# Sheet_1_2021-08-17.net
KiCad netlist of a schematic drawn in Altium Designer
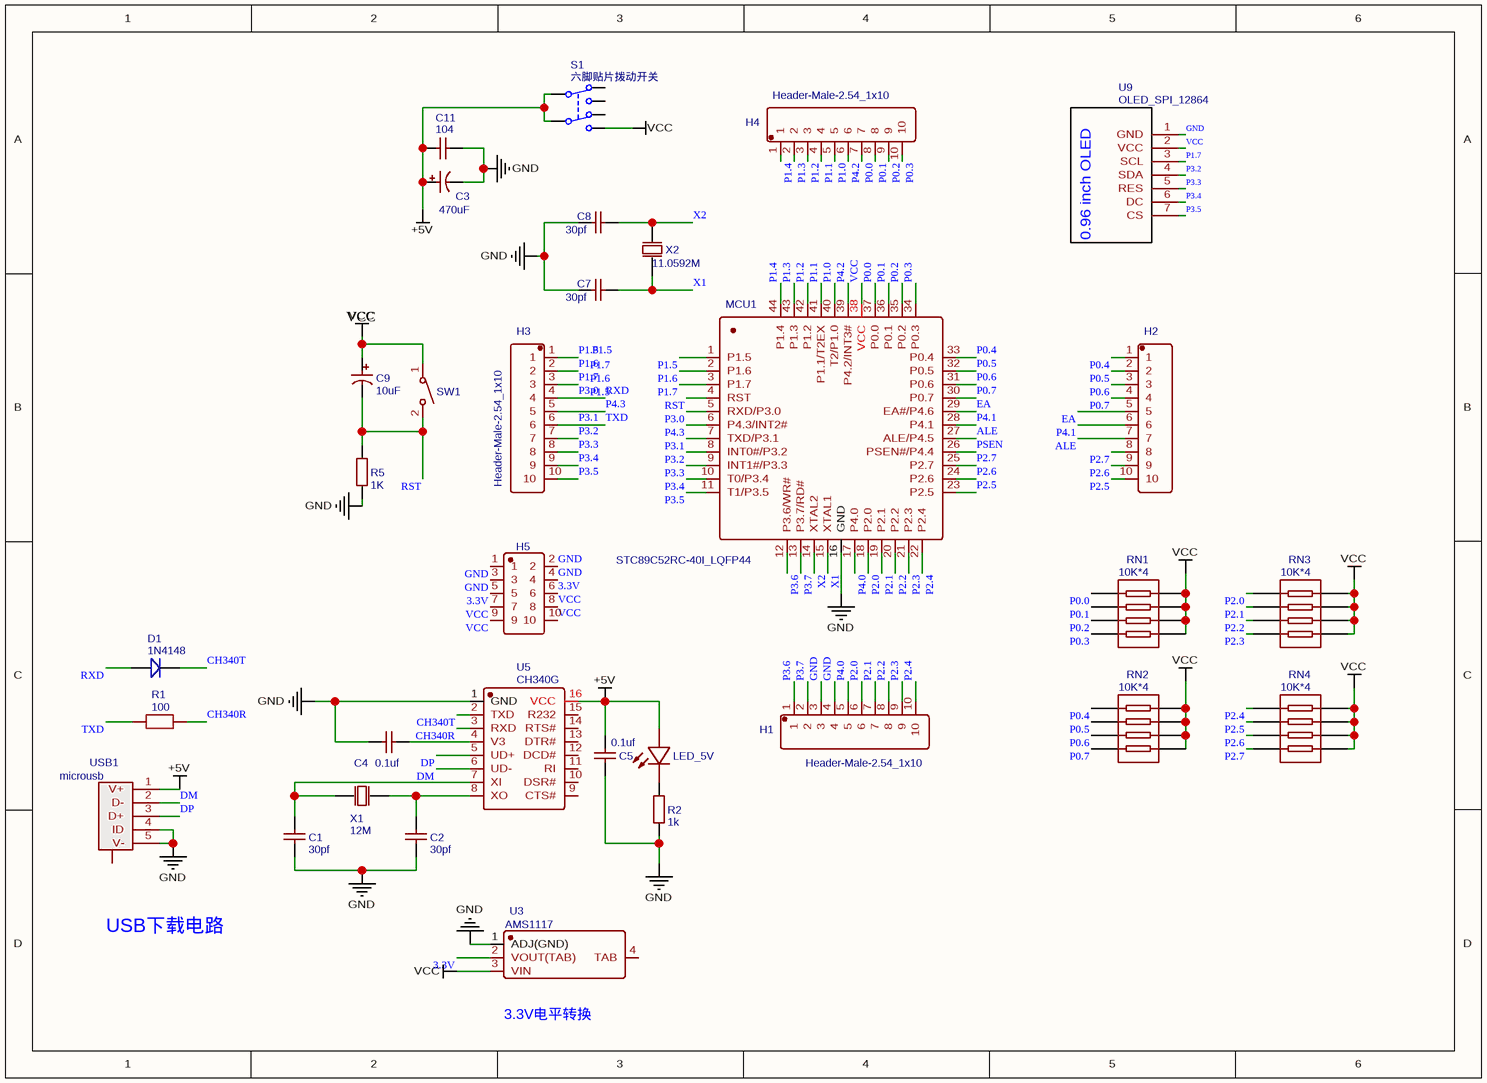
[diagram p0: Sheet_1_2021-08-17.schdoc]

(export (version "E")
  (design (tool "Eeschema 10.0.6"))
  (components
    (comp (ref "C1")
      (value "30pf")
      (fields
        (field (name "BOM_SUPPLIER PART") "C305730")
        (field (name "BOM_MANUFACTURER PART") "CC81-M6S2L1B101KSE")
        (field (name "CONTRIBUTOR") "LCSC")
      )
      (libsource (lib "altium-import") (part "root_1_30pf_"))
    )
    (comp (ref "C2")
      (value "30pf")
      (fields
        (field (name "BOM_SUPPLIER PART") "C305730")
        (field (name "BOM_MANUFACTURER PART") "CC81-M6S2L1B101KSE")
        (field (name "CONTRIBUTOR") "LCSC")
      )
      (libsource (lib "altium-import") (part "root_3_30pf_"))
    )
    (comp (ref "C3")
      (value "470uF")
      (fields
        (field (name "BOM_MANUFACTURER PART") "VEJ471M1CTR-0810")
        (field (name "BOM_SUPPLIER PART") "C176671")
        (field (name "CONTRIBUTOR") "LCSC")
      )
      (libsource (lib "altium-import") (part "root_1_470uF_"))
    )
    (comp (ref "C4")
      (value "0.1uf")
      (fields
        (field (name "BOM_SUPPLIER PART") "C305730")
        (field (name "BOM_MANUFACTURER PART") "CC81-M6S2L1B101KSE")
        (field (name "CONTRIBUTOR") "LCSC")
      )
      (libsource (lib "altium-import") (part "root_2_0.1uf_"))
    )
    (comp (ref "C5")
      (value "0.1uf")
      (fields
        (field (name "BOM_SUPPLIER PART") "C305730")
        (field (name "BOM_MANUFACTURER PART") "CC81-M6S2L1B101KSE")
        (field (name "CONTRIBUTOR") "LCSC")
      )
      (libsource (lib "altium-import") (part "root_1_0.1uf_"))
    )
    (comp (ref "C7")
      (value "30pf")
      (fields
        (field (name "BOM_SUPPLIER PART") "C305730")
        (field (name "BOM_MANUFACTURER PART") "CC81-M6S2L1B101KSE")
        (field (name "CONTRIBUTOR") "LCSC")
      )
      (libsource (lib "altium-import") (part "root_0_30pf_"))
    )
    (comp (ref "C8")
      (value "30pf")
      (fields
        (field (name "BOM_SUPPLIER PART") "C305730")
        (field (name "BOM_MANUFACTURER PART") "CC81-M6S2L1B101KSE")
        (field (name "CONTRIBUTOR") "LCSC")
      )
      (libsource (lib "altium-import") (part "root_0_30pf_"))
    )
    (comp (ref "C9")
      (value "10uF")
      (fields
        (field (name "BOM_MANUFACTURER PART") "VE-100M1ETR-0405")
        (field (name "BOM_SUPPLIER PART") "C134721")
        (field (name "CONTRIBUTOR") "LCSC")
      )
      (libsource (lib "altium-import") (part "root_0_10uF_"))
    )
    (comp (ref "C11")
      (value "104")
      (fields
        (field (name "BOM_SUPPLIER PART") "C305730")
        (field (name "BOM_MANUFACTURER PART") "CC81-M6S2L1B101KSE")
        (field (name "CONTRIBUTOR") "LCSC")
      )
      (libsource (lib "altium-import") (part "root_2_104_"))
    )
    (comp (ref "D1")
      (value "1N4148")
      (fields (field (name "CONTRIBUTOR") "NJDZ"))
      (libsource (lib "altium-import") (part "root_0_1N4148_"))
    )
    (comp (ref "H1")
      (value "Header-Male-2.54_1x10")
      (fields
        (field (name "BOM_MANUFACTURER PART") "Headers  Pins2.54mm1*10P")
        (field (name "BOM_SUPPLIER PART") "C57369")
      )
      (libsource (lib "altium-import") (part "root_3_Header-Male-2.54_1x10_"))
    )
    (comp (ref "H2")
      (value "Header-Male-2.54_1x10")
      (fields
        (field (name "BOM_MANUFACTURER PART") "Headers  Pins2.54mm1*10P")
        (field (name "BOM_SUPPLIER PART") "C57369")
      )
      (libsource (lib "altium-import") (part "root_0_Header-Male-2.54_1x10_"))
    )
    (comp (ref "H3")
      (value "Header-Male-2.54_1x10")
      (fields
        (field (name "BOM_MANUFACTURER PART") "Headers  Pins2.54mm1*10P")
        (field (name "BOM_SUPPLIER PART") "C57369")
      )
      (libsource (lib "") (part "root_0_Header-Male-2.54_1x10__1"))
    )
    (comp (ref "H4")
      (value "Header-Male-2.54_1x10")
      (fields
        (field (name "BOM_MANUFACTURER PART") "Headers  Pins2.54mm1*10P")
        (field (name "BOM_SUPPLIER PART") "C57369")
      )
      (libsource (lib "altium-import") (part "root_1_Header-Male-2.54_1x10_"))
    )
    (comp (ref "H5")
      (value "X6521FV-2×05-C85D32")
      (fields (field (name "BOM_SUPPLIER PART") "C718231") (field (name "CONTRIBUTOR") "LCSC"))
      (libsource (lib "altium-import") (part "root_0_X6521FV-2×05-C85D32_"))
    )
    (comp (ref "LED_5V")
      (value "led Green")
      (fields (field (name "BOM_SUPPLIER PART") "C14641"))
      (libsource (lib "altium-import") (part "root_1_led Green_"))
    )
    (comp (ref "MCU1")
      (value "STC89C52RC-40I_LQFP44")
      (fields
        (field (name "BOM_MANUFACTURER PART") "STC89C52RC-40I")
        (field (name "BOM_SUPPLIER PART") "C8707")
      )
      (libsource (lib "altium-import") (part "root_0_STC89C52RC-40I_LQFP44_"))
    )
    (comp (ref "R1")
      (value "100")
      (fields (field (name "CONTRIBUTOR") "LCEDA_Lib"))
      (libsource (lib "altium-import") (part "root_0_100_"))
    )
    (comp (ref "R2")
      (value "1k")
      (fields
        (field (name "BOM_MANUFACTURER PART") "0603WAF1000T5E")
        (field (name "BOM_SUPPLIER PART") "C22775")
      )
      (libsource (lib "altium-import") (part "root_1_1k_"))
    )
    (comp (ref "R5")
      (value "1K")
      (fields
        (field (name "BOM_MANUFACTURER PART") "0603WAF1000T5E")
        (field (name "BOM_SUPPLIER PART") "C22775")
      )
      (libsource (lib "altium-import") (part "root_1_1K_"))
    )
    (comp (ref "RN1")
      (value "10K*4")
      (fields
        (field (name "BOM_MANUFACTURER PART") "RC-ML08W103JT")
        (field (name "BOM_SUPPLIER PART") "C69593")
        (field (name "CONTRIBUTOR") "amwhibo")
      )
      (libsource (lib "altium-import") (part "root_1_10K*4_"))
    )
    (comp (ref "RN2")
      (value "10K*4")
      (fields
        (field (name "BOM_MANUFACTURER PART") "RC-ML08W103JT")
        (field (name "BOM_SUPPLIER PART") "C69593")
        (field (name "CONTRIBUTOR") "amwhibo")
      )
      (libsource (lib "altium-import") (part "root_1_10K*4_"))
    )
    (comp (ref "RN3")
      (value "10K*4")
      (fields
        (field (name "BOM_MANUFACTURER PART") "RC-ML08W103JT")
        (field (name "BOM_SUPPLIER PART") "C69593")
        (field (name "CONTRIBUTOR") "amwhibo")
      )
      (libsource (lib "altium-import") (part "root_1_10K*4_"))
    )
    (comp (ref "RN4")
      (value "10K*4")
      (fields
        (field (name "BOM_MANUFACTURER PART") "RC-ML08W103JT")
        (field (name "BOM_SUPPLIER PART") "C69593")
        (field (name "CONTRIBUTOR") "amwhibo")
      )
      (libsource (lib "altium-import") (part "root_1_10K*4_"))
    )
    (comp (ref "S1")
      (value "六脚贴片拨动开关")
      (fields (field (name "CONTRIBUTOR") "yds432427"))
      (libsource (lib "altium-import") (part "root_0_六脚贴片拨动开关_"))
    )
    (comp (ref "SW1")
      (value "UK-B0240-W-250-JZ")
      (fields (field (name "BOM_SUPPLIER PART") "C780530") (field (name "CONTRIBUTOR") "LCSC"))
      (libsource (lib "altium-import") (part "root_3_UK-B0240-W-250-JZ_"))
    )
    (comp (ref "U3")
      (value "AMS1117")
      (fields
        (field (name "BOM_SUPPLIER PART") "C347223")
        (field (name "BOM_MANUFACTURER PART") "AMS1117-5.0")
        (field (name "CONTRIBUTOR") "LCSC")
      )
      (libsource (lib "altium-import") (part "root_0_AMS1117_"))
    )
    (comp (ref "U5")
      (value "CH340G")
      (fields (field (name "BOM_SUPPLIER PART") "C14267"))
      (libsource (lib "altium-import") (part "root_0_CH340G_"))
    )
    (comp (ref "U9")
      (value "OLED_SPI_12864")
      (fields
        (field (name "BOM_MANUFACTURER PART") "OLED I2C 12864")
        (field (name "CONTRIBUTOR") "qq137550162")
      )
      (libsource (lib "altium-import") (part "root_3_OLED_SPI_12864_"))
    )
    (comp (ref "USB1")
      (value "microusb")
      (fields
        (field (name "BOM_MANUFACTURER PART") "micro USBFemale")
        (field (name "BOM_SUPPLIER PART") "C10418")
      )
      (libsource (lib "altium-import") (part "root_0_microusb_"))
    )
    (comp (ref "X1")
      (value "12M")
      (fields
        (field (name "BOM_SUPPLIER PART") "C280058")
        (field (name "BOM_MANUFACTURER PART") "B08000J067")
        (field (name "CONTRIBUTOR") "LCSC")
      )
      (libsource (lib "altium-import") (part "root_0_12M_"))
    )
    (comp (ref "X2")
      (value "11.0592M")
      (fields
        (field (name "BOM_SUPPLIER PART") "C280058")
        (field (name "BOM_MANUFACTURER PART") "B08000J067")
        (field (name "CONTRIBUTOR") "LCSC")
      )
      (libsource (lib "altium-import") (part "root_1_11.0592M_"))
    )
  )
  (nets
    (net (code "1") (name "+5V") (class "Default")
      (node (ref "C11") (pin "2") (pinfunction "2_2") (pintype "passive"))
      (node (ref "C3") (pin "1") (pinfunction "1_1") (pintype "passive"))
      (node (ref "C5") (pin "2") (pinfunction "2_2") (pintype "passive"))
      (node (ref "LED_5V") (pin "2") (pinfunction "+_2") (pintype "passive"))
      (node (ref "S1") (pin "2") (pinfunction "COMMON1_2") (pintype "passive"))
      (node (ref "U5") (pin "16") (pinfunction "VCC_16") (pintype "passive"))
      (node (ref "USB1") (pin "1") (pinfunction "V+_1") (pintype "passive"))
    )
    (net (code "2") (name "/3.3V") (class "Default")
      (node (ref "H5") (pin "5") (pinfunction "5_5") (pintype "passive"))
      (node (ref "H5") (pin "6") (pinfunction "6_6") (pintype "passive"))
      (node (ref "U3") (pin "2") (pinfunction "VOUT(TAB)_2") (pintype "passive"))
    )
    (net (code "3") (name "/ALE") (class "Default")
      (node (ref "H2") (pin "7") (pinfunction "7_7") (pintype "passive"))
      (node (ref "MCU1") (pin "27") (pinfunction "ALE/P4.5_27") (pintype "passive"))
    )
    (net (code "4") (name "/CH340R") (class "Default")
      (node (ref "R1") (pin "2") (pinfunction "2_2") (pintype "passive"))
      (node (ref "U5") (pin "3") (pinfunction "RXD_3") (pintype "passive"))
    )
    (net (code "5") (name "/CH340T") (class "Default")
      (node (ref "D1") (pin "2") (pinfunction "2_2") (pintype "passive"))
      (node (ref "U5") (pin "2") (pinfunction "TXD_2") (pintype "passive"))
    )
    (net (code "6") (name "/DM") (class "Default")
      (node (ref "U5") (pin "6") (pinfunction "UD-_6") (pintype "passive"))
      (node (ref "USB1") (pin "2") (pinfunction "D-_2") (pintype "passive"))
    )
    (net (code "7") (name "/DP") (class "Default")
      (node (ref "U5") (pin "5") (pinfunction "UD+_5") (pintype "passive"))
      (node (ref "USB1") (pin "3") (pinfunction "D+_3") (pintype "passive"))
    )
    (net (code "8") (name "/EA") (class "Default")
      (node (ref "H2") (pin "5") (pinfunction "5_5") (pintype "passive"))
      (node (ref "MCU1") (pin "29") (pinfunction "EA#/P4.6_29") (pintype "passive"))
    )
    (net (code "9") (name "/P0.0") (class "Default")
      (node (ref "H4") (pin "7") (pinfunction "7_7") (pintype "passive"))
      (node (ref "MCU1") (pin "37") (pinfunction "P0.0_37") (pintype "passive"))
      (node (ref "RN1") (pin "4") (pinfunction "4_4") (pintype "passive"))
    )
    (net (code "10") (name "/P0.1") (class "Default")
      (node (ref "H4") (pin "8") (pinfunction "8_8") (pintype "passive"))
      (node (ref "MCU1") (pin "36") (pinfunction "P0.1_36") (pintype "passive"))
      (node (ref "RN1") (pin "3") (pinfunction "3_3") (pintype "passive"))
    )
    (net (code "11") (name "/P0.2") (class "Default")
      (node (ref "H4") (pin "9") (pinfunction "9_9") (pintype "passive"))
      (node (ref "MCU1") (pin "35") (pinfunction "P0.2_35") (pintype "passive"))
      (node (ref "RN1") (pin "2") (pinfunction "2_2") (pintype "passive"))
    )
    (net (code "12") (name "/P0.3") (class "Default")
      (node (ref "H4") (pin "10") (pinfunction "10_10") (pintype "passive"))
      (node (ref "MCU1") (pin "34") (pinfunction "P0.3_34") (pintype "passive"))
      (node (ref "RN1") (pin "1") (pinfunction "1_1") (pintype "passive"))
    )
    (net (code "13") (name "/P0.4") (class "Default")
      (node (ref "H2") (pin "1") (pinfunction "1_1") (pintype "passive"))
      (node (ref "MCU1") (pin "33") (pinfunction "P0.4_33") (pintype "passive"))
      (node (ref "RN2") (pin "4") (pinfunction "4_4") (pintype "passive"))
    )
    (net (code "14") (name "/P0.5") (class "Default")
      (node (ref "H2") (pin "2") (pinfunction "2_2") (pintype "passive"))
      (node (ref "MCU1") (pin "32") (pinfunction "P0.5_32") (pintype "passive"))
      (node (ref "RN2") (pin "3") (pinfunction "3_3") (pintype "passive"))
    )
    (net (code "15") (name "/P0.6") (class "Default")
      (node (ref "H2") (pin "3") (pinfunction "3_3") (pintype "passive"))
      (node (ref "MCU1") (pin "31") (pinfunction "P0.6_31") (pintype "passive"))
      (node (ref "RN2") (pin "2") (pinfunction "2_2") (pintype "passive"))
    )
    (net (code "16") (name "/P0.7") (class "Default")
      (node (ref "H2") (pin "4") (pinfunction "4_4") (pintype "passive"))
      (node (ref "MCU1") (pin "30") (pinfunction "P0.7_30") (pintype "passive"))
      (node (ref "RN2") (pin "1") (pinfunction "1_1") (pintype "passive"))
    )
    (net (code "17") (name "/P1.0") (class "Default")
      (node (ref "H4") (pin "5") (pinfunction "5_5") (pintype "passive"))
      (node (ref "MCU1") (pin "40") (pinfunction "T2/P1.0_40") (pintype "passive"))
    )
    (net (code "18") (name "/P1.1") (class "Default")
      (node (ref "H4") (pin "4") (pinfunction "4_4") (pintype "passive"))
      (node (ref "MCU1") (pin "41") (pinfunction "P1.1/T2EX_41") (pintype "passive"))
    )
    (net (code "19") (name "/P1.2") (class "Default")
      (node (ref "H4") (pin "3") (pinfunction "3_3") (pintype "passive"))
      (node (ref "MCU1") (pin "42") (pinfunction "P1.2_42") (pintype "passive"))
    )
    (net (code "20") (name "/P1.3") (class "Default")
      (node (ref "H4") (pin "2") (pinfunction "2_2") (pintype "passive"))
      (node (ref "MCU1") (pin "43") (pinfunction "P1.3_43") (pintype "passive"))
    )
    (net (code "21") (name "/P1.4") (class "Default")
      (node (ref "H4") (pin "1") (pinfunction "1_1") (pintype "passive"))
      (node (ref "MCU1") (pin "44") (pinfunction "P1.4_44") (pintype "passive"))
    )
    (net (code "22") (name "/P1.5") (class "Default")
      (node (ref "H3") (pin "1") (pinfunction "1_1") (pintype "passive"))
      (node (ref "MCU1") (pin "1") (pinfunction "P1.5_1") (pintype "passive"))
    )
    (net (code "23") (name "/P1.6") (class "Default")
      (node (ref "H3") (pin "2") (pinfunction "2_2") (pintype "passive"))
      (node (ref "MCU1") (pin "2") (pinfunction "P1.6_2") (pintype "passive"))
    )
    (net (code "24") (name "/P1.7") (class "Default")
      (node (ref "H3") (pin "3") (pinfunction "3_3") (pintype "passive"))
      (node (ref "MCU1") (pin "3") (pinfunction "P1.7_3") (pintype "passive"))
      (node (ref "U9") (pin "3") (pinfunction "SCL_3") (pintype "passive"))
    )
    (net (code "25") (name "/P2.0") (class "Default")
      (node (ref "H1") (pin "6") (pinfunction "6_6") (pintype "passive"))
      (node (ref "MCU1") (pin "18") (pinfunction "P2.0_18") (pintype "passive"))
      (node (ref "RN3") (pin "4") (pinfunction "4_4") (pintype "passive"))
    )
    (net (code "26") (name "/P2.1") (class "Default")
      (node (ref "H1") (pin "7") (pinfunction "7_7") (pintype "passive"))
      (node (ref "MCU1") (pin "19") (pinfunction "P2.1_19") (pintype "passive"))
      (node (ref "RN3") (pin "3") (pinfunction "3_3") (pintype "passive"))
    )
    (net (code "27") (name "/P2.2") (class "Default")
      (node (ref "H1") (pin "8") (pinfunction "8_8") (pintype "passive"))
      (node (ref "MCU1") (pin "20") (pinfunction "P2.2_20") (pintype "passive"))
      (node (ref "RN3") (pin "2") (pinfunction "2_2") (pintype "passive"))
    )
    (net (code "28") (name "/P2.3") (class "Default")
      (node (ref "H1") (pin "9") (pinfunction "9_9") (pintype "passive"))
      (node (ref "MCU1") (pin "21") (pinfunction "P2.3_21") (pintype "passive"))
      (node (ref "RN3") (pin "1") (pinfunction "1_1") (pintype "passive"))
    )
    (net (code "29") (name "/P2.4") (class "Default")
      (node (ref "H1") (pin "10") (pinfunction "10_10") (pintype "passive"))
      (node (ref "MCU1") (pin "22") (pinfunction "P2.4_22") (pintype "passive"))
      (node (ref "RN4") (pin "4") (pinfunction "4_4") (pintype "passive"))
    )
    (net (code "30") (name "/P2.5") (class "Default")
      (node (ref "H2") (pin "10") (pinfunction "10_10") (pintype "passive"))
      (node (ref "MCU1") (pin "23") (pinfunction "P2.5_23") (pintype "passive"))
      (node (ref "RN4") (pin "3") (pinfunction "3_3") (pintype "passive"))
    )
    (net (code "31") (name "/P2.6") (class "Default")
      (node (ref "H2") (pin "9") (pinfunction "9_9") (pintype "passive"))
      (node (ref "MCU1") (pin "24") (pinfunction "P2.6_24") (pintype "passive"))
      (node (ref "RN4") (pin "2") (pinfunction "2_2") (pintype "passive"))
    )
    (net (code "32") (name "/P2.7") (class "Default")
      (node (ref "H2") (pin "8") (pinfunction "8_8") (pintype "passive"))
      (node (ref "MCU1") (pin "25") (pinfunction "P2.7_25") (pintype "passive"))
      (node (ref "RN4") (pin "1") (pinfunction "1_1") (pintype "passive"))
    )
    (net (code "33") (name "/P3.0") (class "Default")
      (node (ref "D1") (pin "1") (pinfunction "1_1") (pintype "passive"))
      (node (ref "H3") (pin "4") (pinfunction "4_4") (pintype "passive"))
      (node (ref "MCU1") (pin "5") (pinfunction "RXD/P3.0_5") (pintype "passive"))
    )
    (net (code "34") (name "/P3.1") (class "Default")
      (node (ref "H3") (pin "6") (pinfunction "6_6") (pintype "passive"))
      (node (ref "MCU1") (pin "7") (pinfunction "TXD/P3.1_7") (pintype "passive"))
      (node (ref "R1") (pin "1") (pinfunction "1_1") (pintype "passive"))
    )
    (net (code "35") (name "/P3.2") (class "Default")
      (node (ref "H3") (pin "7") (pinfunction "7_7") (pintype "passive"))
      (node (ref "MCU1") (pin "8") (pinfunction "INT0#/P3.2_8") (pintype "passive"))
      (node (ref "U9") (pin "4") (pinfunction "SDA_4") (pintype "passive"))
    )
    (net (code "36") (name "/P3.3") (class "Default")
      (node (ref "H3") (pin "8") (pinfunction "8_8") (pintype "passive"))
      (node (ref "MCU1") (pin "9") (pinfunction "INT1#/P3.3_9") (pintype "passive"))
      (node (ref "U9") (pin "5") (pinfunction "RES_5") (pintype "passive"))
    )
    (net (code "37") (name "/P3.4") (class "Default")
      (node (ref "H3") (pin "9") (pinfunction "9_9") (pintype "passive"))
      (node (ref "MCU1") (pin "10") (pinfunction "T0/P3.4_10") (pintype "passive"))
      (node (ref "U9") (pin "6") (pinfunction "DC_6") (pintype "passive"))
    )
    (net (code "38") (name "/P3.5") (class "Default")
      (node (ref "H3") (pin "10") (pinfunction "10_10") (pintype "passive"))
      (node (ref "MCU1") (pin "11") (pinfunction "T1/P3.5_11") (pintype "passive"))
      (node (ref "U9") (pin "7") (pinfunction "CS_7") (pintype "passive"))
    )
    (net (code "39") (name "/P3.6") (class "Default")
      (node (ref "H1") (pin "1") (pinfunction "1_1") (pintype "passive"))
      (node (ref "MCU1") (pin "12") (pinfunction "P3.6/WR#_12") (pintype "passive"))
    )
    (net (code "40") (name "/P3.7") (class "Default")
      (node (ref "H1") (pin "2") (pinfunction "2_2") (pintype "passive"))
      (node (ref "MCU1") (pin "13") (pinfunction "P3.7/RD#_13") (pintype "passive"))
    )
    (net (code "41") (name "/P4.0") (class "Default")
      (node (ref "H1") (pin "5") (pinfunction "5_5") (pintype "passive"))
      (node (ref "MCU1") (pin "17") (pinfunction "P4.0_17") (pintype "passive"))
    )
    (net (code "42") (name "/P4.1") (class "Default")
      (node (ref "H2") (pin "6") (pinfunction "6_6") (pintype "passive"))
      (node (ref "MCU1") (pin "28") (pinfunction "P4.1_28") (pintype "passive"))
    )
    (net (code "43") (name "/P4.2") (class "Default")
      (node (ref "H4") (pin "6") (pinfunction "6_6") (pintype "passive"))
      (node (ref "MCU1") (pin "39") (pinfunction "P4.2/INT3#_39") (pintype "passive"))
    )
    (net (code "44") (name "/P4.3") (class "Default")
      (node (ref "H3") (pin "5") (pinfunction "5_5") (pintype "passive"))
      (node (ref "MCU1") (pin "6") (pinfunction "P4.3/INT2#_6") (pintype "passive"))
    )
    (net (code "45") (name "/PSEN") (class "Default")
      (node (ref "MCU1") (pin "26") (pinfunction "PSEN#/P4.4_26") (pintype "passive"))
    )
    (net (code "46") (name "/RST") (class "Default")
      (node (ref "C9") (pin "2") (pinfunction "2_2") (pintype "passive"))
      (node (ref "MCU1") (pin "4") (pinfunction "RST_4") (pintype "passive"))
      (node (ref "R5") (pin "2") (pinfunction "2_2") (pintype "passive"))
      (node (ref "SW1") (pin "2") (pinfunction "2_2") (pintype "passive"))
    )
    (net (code "47") (name "/X1") (class "Default")
      (node (ref "C7") (pin "2") (pinfunction "2_2") (pintype "passive"))
      (node (ref "MCU1") (pin "15") (pinfunction "XTAL1_15") (pintype "passive"))
      (node (ref "X2") (pin "1") (pinfunction "OSC1_1") (pintype "passive"))
    )
    (net (code "48") (name "/X2") (class "Default")
      (node (ref "C8") (pin "2") (pinfunction "2_2") (pintype "passive"))
      (node (ref "MCU1") (pin "14") (pinfunction "XTAL2_14") (pintype "passive"))
      (node (ref "X2") (pin "2") (pinfunction "OSC2_2") (pintype "passive"))
    )
    (net (code "49") (name "GND") (class "Default")
      (node (ref "C1") (pin "1") (pinfunction "1_1") (pintype "passive"))
      (node (ref "C11") (pin "1") (pinfunction "1_1") (pintype "passive"))
      (node (ref "C2") (pin "2") (pinfunction "2_2") (pintype "passive"))
      (node (ref "C3") (pin "2") (pinfunction "2_2") (pintype "passive"))
      (node (ref "C4") (pin "2") (pinfunction "2_2") (pintype "passive"))
      (node (ref "C5") (pin "1") (pinfunction "1_1") (pintype "passive"))
      (node (ref "C7") (pin "1") (pinfunction "1_1") (pintype "passive"))
      (node (ref "C8") (pin "1") (pinfunction "1_1") (pintype "passive"))
      (node (ref "H1") (pin "3") (pinfunction "3_3") (pintype "passive"))
      (node (ref "H1") (pin "4") (pinfunction "4_4") (pintype "passive"))
      (node (ref "H5") (pin "1") (pinfunction "1_1") (pintype "passive"))
      (node (ref "H5") (pin "2") (pinfunction "2_2") (pintype "passive"))
      (node (ref "H5") (pin "3") (pinfunction "3_3") (pintype "passive"))
      (node (ref "H5") (pin "4") (pinfunction "4_4") (pintype "passive"))
      (node (ref "MCU1") (pin "16") (pinfunction "GND_16") (pintype "passive"))
      (node (ref "R2") (pin "1") (pinfunction "1_1") (pintype "passive"))
      (node (ref "R5") (pin "1") (pinfunction "1_1") (pintype "passive"))
      (node (ref "U3") (pin "1") (pinfunction "ADJ(GND)_1") (pintype "passive"))
      (node (ref "U5") (pin "1") (pinfunction "GND_1") (pintype "passive"))
      (node (ref "U9") (pin "1") (pinfunction "GND_1") (pintype "passive"))
      (node (ref "USB1") (pin "4") (pinfunction "ID_4") (pintype "passive"))
      (node (ref "USB1") (pin "5") (pinfunction "V-_5") (pintype "passive"))
    )
    (net (code "50") (name "Net-(LED_5V--)") (class "Default")
      (node (ref "LED_5V") (pin "1") (pinfunction "-_1") (pintype "passive"))
      (node (ref "R2") (pin "2") (pinfunction "2_2") (pintype "passive"))
    )
    (net (code "51") (name "Net-(U5-V3)") (class "Default")
      (node (ref "C4") (pin "1") (pinfunction "1_1") (pintype "passive"))
      (node (ref "U5") (pin "4") (pinfunction "V3_4") (pintype "passive"))
    )
    (net (code "52") (name "Net-(U5-XI)") (class "Default")
      (node (ref "C1") (pin "2") (pinfunction "2_2") (pintype "passive"))
      (node (ref "U5") (pin "7") (pinfunction "XI_7") (pintype "passive"))
      (node (ref "X1") (pin "1") (pinfunction "OSC1_1") (pintype "passive"))
    )
    (net (code "53") (name "Net-(U5-XO)") (class "Default")
      (node (ref "C2") (pin "1") (pinfunction "1_1") (pintype "passive"))
      (node (ref "U5") (pin "8") (pinfunction "XO_8") (pintype "passive"))
      (node (ref "X1") (pin "2") (pinfunction "OSC2_2") (pintype "passive"))
    )
    (net (code "54") (name "VCC") (class "Default")
      (node (ref "C9") (pin "1") (pinfunction "1_1") (pintype "passive"))
      (node (ref "H5") (pin "10") (pinfunction "10_10") (pintype "passive"))
      (node (ref "H5") (pin "7") (pinfunction "7_7") (pintype "passive"))
      (node (ref "H5") (pin "8") (pinfunction "8_8") (pintype "passive"))
      (node (ref "H5") (pin "9") (pinfunction "9_9") (pintype "passive"))
      (node (ref "MCU1") (pin "38") (pinfunction "VCC_38") (pintype "passive"))
      (node (ref "RN1") (pin "5") (pinfunction "5_5") (pintype "passive"))
      (node (ref "RN1") (pin "6") (pinfunction "6_6") (pintype "passive"))
      (node (ref "RN1") (pin "7") (pinfunction "7_7") (pintype "passive"))
      (node (ref "RN1") (pin "8") (pinfunction "8_8") (pintype "passive"))
      (node (ref "RN2") (pin "5") (pinfunction "5_5") (pintype "passive"))
      (node (ref "RN2") (pin "6") (pinfunction "6_6") (pintype "passive"))
      (node (ref "RN2") (pin "7") (pinfunction "7_7") (pintype "passive"))
      (node (ref "RN2") (pin "8") (pinfunction "8_8") (pintype "passive"))
      (node (ref "RN3") (pin "5") (pinfunction "5_5") (pintype "passive"))
      (node (ref "RN3") (pin "6") (pinfunction "6_6") (pintype "passive"))
      (node (ref "RN3") (pin "7") (pinfunction "7_7") (pintype "passive"))
      (node (ref "RN3") (pin "8") (pinfunction "8_8") (pintype "passive"))
      (node (ref "RN4") (pin "5") (pinfunction "5_5") (pintype "passive"))
      (node (ref "RN4") (pin "6") (pinfunction "6_6") (pintype "passive"))
      (node (ref "RN4") (pin "7") (pinfunction "7_7") (pintype "passive"))
      (node (ref "RN4") (pin "8") (pinfunction "8_8") (pintype "passive"))
      (node (ref "S1") (pin "3") (pinfunction "NO1_3") (pintype "passive"))
      (node (ref "SW1") (pin "1") (pinfunction "1_1") (pintype "passive"))
      (node (ref "U3") (pin "3") (pinfunction "VIN_3") (pintype "passive"))
      (node (ref "U9") (pin "2") (pinfunction "VCC_2") (pintype "passive"))
    )
    (net (code "55") (name "unconnected-(S1-NC1-Pad1)") (class "Default")
      (node (ref "S1") (pin "1") (pinfunction "NC1_1") (pintype "passive"))
    )
    (net (code "56") (name "unconnected-(S1-NC1-Pad1)_1") (class "Default")
      (node (ref "S1") (pin "1") (pinfunction "NC1_1") (pintype "passive"))
    )
    (net (code "57") (name "unconnected-(S1-NO1-Pad3)") (class "Default")
      (node (ref "S1") (pin "3") (pinfunction "NO1_3") (pintype "passive"))
    )
    (net (code "58") (name "unconnected-(U3-TAB-Pad4)") (class "Default")
      (node (ref "U3") (pin "4") (pinfunction "TAB_4") (pintype "passive"))
    )
    (net (code "59") (name "unconnected-(U5-CTS#-Pad9)") (class "Default")
      (node (ref "U5") (pin "9") (pinfunction "CTS#_9") (pintype "passive"))
    )
    (net (code "60") (name "unconnected-(U5-DCD#-Pad12)") (class "Default")
      (node (ref "U5") (pin "12") (pinfunction "DCD#_12") (pintype "passive"))
    )
    (net (code "61") (name "unconnected-(U5-DSR#-Pad10)") (class "Default")
      (node (ref "U5") (pin "10") (pinfunction "DSR#_10") (pintype "passive"))
    )
    (net (code "62") (name "unconnected-(U5-DTR#-Pad13)") (class "Default")
      (node (ref "U5") (pin "13") (pinfunction "DTR#_13") (pintype "passive"))
    )
    (net (code "63") (name "unconnected-(U5-R232-Pad15)") (class "Default")
      (node (ref "U5") (pin "15") (pinfunction "R232_15") (pintype "passive"))
    )
    (net (code "64") (name "unconnected-(U5-RI-Pad11)") (class "Default")
      (node (ref "U5") (pin "11") (pinfunction "RI_11") (pintype "passive"))
    )
    (net (code "65") (name "unconnected-(U5-RTS#-Pad14)") (class "Default")
      (node (ref "U5") (pin "14") (pinfunction "RTS#_14") (pintype "passive"))
    )
    (net (code "66") (name "unconnected-(USB1-MTN-Pad0)") (class "Default")
      (node (ref "USB1") (pin "0") (pinfunction "MTN_0") (pintype "passive"))
    )
  )
)
